# Keyboard.net
KiCad netlist of a schematic drawn in Altium Designer
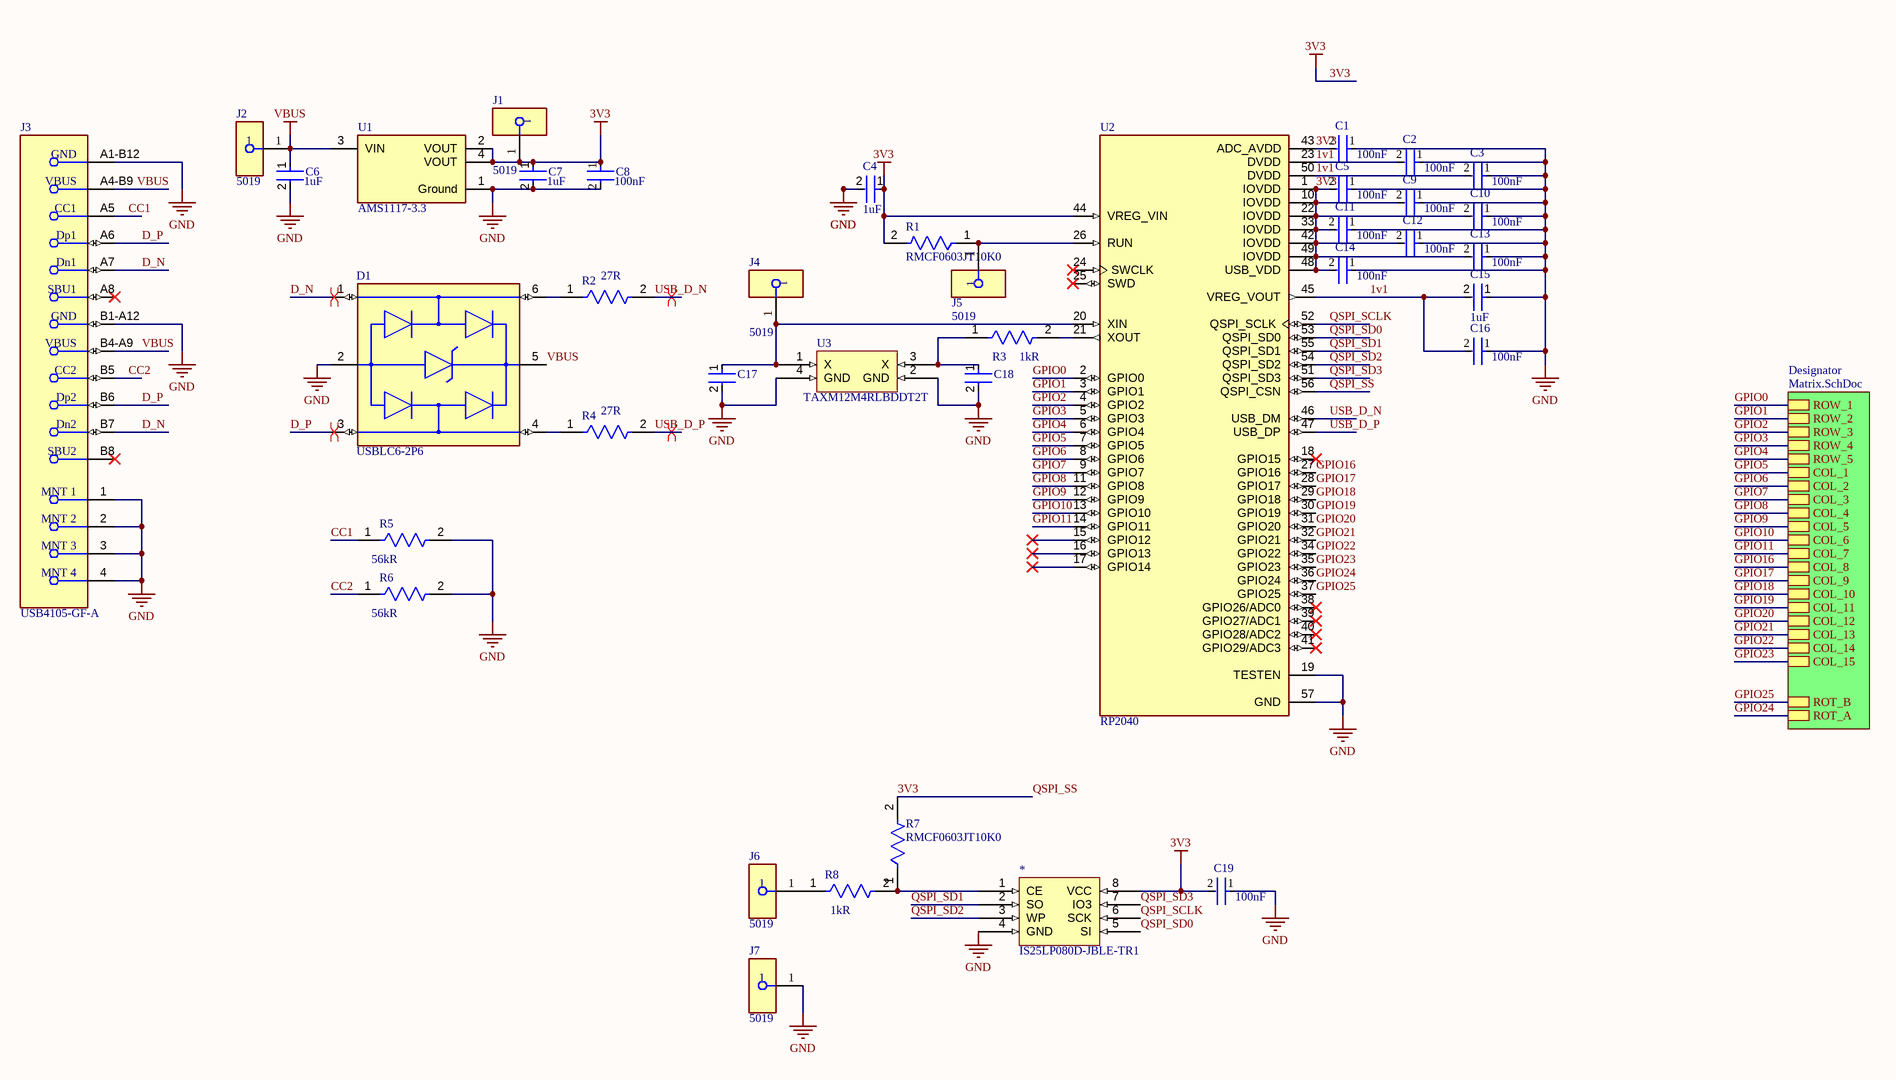
[diagram p0: Keyboard.SchDoc]

(export (version "E")
  (design (tool "Eeschema 10.0.6"))
  (components
    (comp (ref "*")
      (value "IS25LP080D-JBLE-TR1")
      (footprint "SOIC127P1030X265-8N")
      (description "Flash")
      (libsource (lib "Brian Tan") (part "New symbol 1"))
    )
    (comp (ref "C1")
      (value "GRM155R71C104KA88J")
      (footprint "FP-GRM155-0_05-MFG")
      (fields
        (field (name "VOLTAGE") "16V")
        (field (name "TOLERANCE") "10%")
        (field (name "CAPACITANCE") "100nF")
      )
      (libsource (lib "Altium Content Vault") (part "b4654b650e69147ec39a6b967a45e02"))
    )
    (comp (ref "C2")
      (value "GRM155R71C104KA88J")
      (footprint "FP-GRM155-0_05-MFG")
      (fields
        (field (name "VOLTAGE") "16V")
        (field (name "TOLERANCE") "10%")
        (field (name "CAPACITANCE") "100nF")
      )
      (libsource (lib "Altium Content Vault") (part "b4654b650e69147ec39a6b967a45e02"))
    )
    (comp (ref "C3")
      (value "GRM155R71C104KA88J")
      (footprint "FP-GRM155-0_05-MFG")
      (fields
        (field (name "VOLTAGE") "16V")
        (field (name "TOLERANCE") "10%")
        (field (name "CAPACITANCE") "100nF")
      )
      (libsource (lib "Altium Content Vault") (part "b4654b650e69147ec39a6b967a45e02"))
    )
    (comp (ref "C4")
      (value "CL10A105KO8NNNC")
      (footprint "FP-CL10-IPC_A")
      (description "Cap Ceramic 1uF 16V X5R ±10% Pad SMD 0603 +85°C T/R")
      (fields
        (field (name "CAPACITANCE") "1uF")
        (field (name "TOLERANCE") "10%")
        (field (name "VOLTAGE") "16V")
      )
      (libsource (lib "Altium Content Vault") (part "b4654b650e69147ec39a6b967a45e02"))
    )
    (comp (ref "C5")
      (value "GRM155R71C104KA88J")
      (footprint "FP-GRM155-0_05-MFG")
      (fields
        (field (name "VOLTAGE") "16V")
        (field (name "TOLERANCE") "10%")
        (field (name "CAPACITANCE") "100nF")
      )
      (libsource (lib "Altium Content Vault") (part "b4654b650e69147ec39a6b967a45e02"))
    )
    (comp (ref "C6")
      (value "CL10A105KO8NNNC")
      (footprint "FP-CL10-IPC_A")
      (description "Cap Ceramic 1uF 16V X5R ±10% Pad SMD 0603 +85°C T/R")
      (fields
        (field (name "CAPACITANCE") "1uF")
        (field (name "TOLERANCE") "10%")
        (field (name "VOLTAGE") "16V")
      )
      (libsource (lib "Altium Content Vault") (part "b4654b650e69147ec39a6b967a45e02"))
    )
    (comp (ref "C7")
      (value "CL10A105KO8NNNC")
      (footprint "FP-CL10-IPC_A")
      (description "Cap Ceramic 1uF 16V X5R ±10% Pad SMD 0603 +85°C T/R")
      (fields
        (field (name "CAPACITANCE") "1uF")
        (field (name "TOLERANCE") "10%")
        (field (name "VOLTAGE") "16V")
      )
      (libsource (lib "Altium Content Vault") (part "b4654b650e69147ec39a6b967a45e02"))
    )
    (comp (ref "C8")
      (value "GRM155R71C104KA88J")
      (footprint "FP-GRM155-0_05-MFG")
      (fields
        (field (name "VOLTAGE") "16V")
        (field (name "TOLERANCE") "10%")
        (field (name "CAPACITANCE") "100nF")
      )
      (libsource (lib "Altium Content Vault") (part "b4654b650e69147ec39a6b967a45e02"))
    )
    (comp (ref "C9")
      (value "GRM155R71C104KA88J")
      (footprint "FP-GRM155-0_05-MFG")
      (fields
        (field (name "VOLTAGE") "16V")
        (field (name "TOLERANCE") "10%")
        (field (name "CAPACITANCE") "100nF")
      )
      (libsource (lib "Altium Content Vault") (part "b4654b650e69147ec39a6b967a45e02"))
    )
    (comp (ref "C10")
      (value "GRM155R71C104KA88J")
      (footprint "FP-GRM155-0_05-MFG")
      (fields
        (field (name "VOLTAGE") "16V")
        (field (name "TOLERANCE") "10%")
        (field (name "CAPACITANCE") "100nF")
      )
      (libsource (lib "Altium Content Vault") (part "b4654b650e69147ec39a6b967a45e02"))
    )
    (comp (ref "C11")
      (value "GRM155R71C104KA88J")
      (footprint "FP-GRM155-0_05-MFG")
      (fields
        (field (name "VOLTAGE") "16V")
        (field (name "TOLERANCE") "10%")
        (field (name "CAPACITANCE") "100nF")
      )
      (libsource (lib "Altium Content Vault") (part "b4654b650e69147ec39a6b967a45e02"))
    )
    (comp (ref "C12")
      (value "GRM155R71C104KA88J")
      (footprint "FP-GRM155-0_05-MFG")
      (fields
        (field (name "VOLTAGE") "16V")
        (field (name "TOLERANCE") "10%")
        (field (name "CAPACITANCE") "100nF")
      )
      (libsource (lib "Altium Content Vault") (part "b4654b650e69147ec39a6b967a45e02"))
    )
    (comp (ref "C13")
      (value "GRM155R71C104KA88J")
      (footprint "FP-GRM155-0_05-MFG")
      (fields
        (field (name "VOLTAGE") "16V")
        (field (name "TOLERANCE") "10%")
        (field (name "CAPACITANCE") "100nF")
      )
      (libsource (lib "Altium Content Vault") (part "b4654b650e69147ec39a6b967a45e02"))
    )
    (comp (ref "C14")
      (value "GRM155R71C104KA88J")
      (footprint "FP-GRM155-0_05-MFG")
      (fields
        (field (name "VOLTAGE") "16V")
        (field (name "TOLERANCE") "10%")
        (field (name "CAPACITANCE") "100nF")
      )
      (libsource (lib "Altium Content Vault") (part "b4654b650e69147ec39a6b967a45e02"))
    )
    (comp (ref "C15")
      (value "CL10A105KO8NNNC")
      (footprint "FP-CL10-IPC_A")
      (description "Cap Ceramic 1uF 16V X5R ±10% Pad SMD 0603 +85°C T/R")
      (fields
        (field (name "CAPACITANCE") "1uF")
        (field (name "TOLERANCE") "10%")
        (field (name "VOLTAGE") "16V")
      )
      (libsource (lib "Altium Content Vault") (part "b4654b650e69147ec39a6b967a45e02"))
    )
    (comp (ref "C16")
      (value "GRM155R71C104KA88J")
      (footprint "FP-GRM155-0_05-MFG")
      (fields
        (field (name "VOLTAGE") "16V")
        (field (name "TOLERANCE") "10%")
        (field (name "CAPACITANCE") "100nF")
      )
      (libsource (lib "Altium Content Vault") (part "b4654b650e69147ec39a6b967a45e02"))
    )
    (comp (ref "C17")
      (value "GQM2195C2E320JB12D")
      (footprint "FP-GQM219-0_15-IPC_C")
      (description "Ceramic Capacitor 32pF ±5% 250VDC C0G 0805 Paper T/R")
      (libsource (lib "Altium Content Vault") (part "b4654b650e69147ec39a6b967a45e02"))
    )
    (comp (ref "C18")
      (value "GQM2195C2E320JB12D")
      (footprint "FP-GQM219-0_15-IPC_C")
      (description "Ceramic Capacitor 32pF ±5% 250VDC C0G 0805 Paper T/R")
      (libsource (lib "Altium Content Vault") (part "b4654b650e69147ec39a6b967a45e02"))
    )
    (comp (ref "C19")
      (value "GRM155R71C104KA88J")
      (footprint "FP-GRM155-0_05-MFG")
      (fields
        (field (name "VOLTAGE") "16V")
        (field (name "TOLERANCE") "10%")
        (field (name "CAPACITANCE") "100nF")
      )
      (libsource (lib "Altium Content Vault") (part "b4654b650e69147ec39a6b967a45e02"))
    )
    (comp (ref "D1")
      (value "USBLC6-2P6")
      (footprint "FP-SOT-666-MFG")
      (description "TVS DIODE 5.25V 17V SOT666")
      (libsource (lib "Altium Content Vault") (part "c871e55f7e3243d341edbd671b98d92"))
    )
    (comp (ref "J1")
      (value "5019")
      (footprint "FP-5019-MFG")
      (libsource (lib "") (part "98815daf2f2c152b0c43f5ab9800df6_2"))
    )
    (comp (ref "J2")
      (value "5019")
      (footprint "FP-5019-MFG")
      (libsource (lib "Altium Content Vault") (part "98815daf2f2c152b0c43f5ab9800df6"))
    )
    (comp (ref "J3")
      (value "USB4105-GF-A")
      (footprint "FP-USB4105-GF-A-MFG")
      (description "CONN RCPT USB2.0 TYPEC 5A")
      (fields
        (field (name "MANUFACTURER") "GCT")
        (field (name "OCTOPART") "https://octopart.com/usb4105-gf-a-gct-106627878")
      )
      (libsource (lib "Altium Content Vault") (part "e7c17a616881a82b79941196b4bec10"))
    )
    (comp (ref "J4")
      (value "5019")
      (footprint "FP-5019-MFG")
      (libsource (lib "") (part "98815daf2f2c152b0c43f5ab9800df6_2"))
    )
    (comp (ref "J5")
      (value "5019")
      (footprint "FP-5019-MFG")
      (libsource (lib "") (part "98815daf2f2c152b0c43f5ab9800df6_1"))
    )
    (comp (ref "J6")
      (value "5019")
      (footprint "FP-5019-MFG")
      (libsource (lib "Altium Content Vault") (part "98815daf2f2c152b0c43f5ab9800df6"))
    )
    (comp (ref "J7")
      (value "5019")
      (footprint "FP-5019-MFG")
      (libsource (lib "Altium Content Vault") (part "98815daf2f2c152b0c43f5ab9800df6"))
    )
    (comp (ref "R1")
      (value "RMCF0603JT10K0")
      (footprint "FP-RMCF0603-IPC_C")
      (description "10kΩ ±5% 0.1W 0603 Thick Film Chip Resistor AEC-Q200 compliant")
      (fields (field (name "TOLERANCE") "5%"))
      (libsource (lib "Altium Content Vault") (part "1029c3af85768c4190bb7ad29bc67b5"))
    )
    (comp (ref "R2")
      (value "RMCF0603FT27R0")
      (footprint "FP-RMCF0603-IPC_B")
      (description "27Ω ±1% 0.1W 0603 Thick Film Chip Resistor AEC-Q200 compliant")
      (fields (field (name "RESISTANCE") "27R") (field (name "TOLERANCE") "1%"))
      (libsource (lib "Altium Content Vault") (part "1029c3af85768c4190bb7ad29bc67b5"))
    )
    (comp (ref "R3")
      (value "RC0603FR-071KL")
      (footprint "FP-RC0603-0_55-IPC_C")
      (description "RES 1K OHM 1% 1/10W 0603")
      (fields (field (name "RESISTANCE") "1kR") (field (name "TOLERANCE") "1%"))
      (libsource (lib "Altium Content Vault") (part "1029c3af85768c4190bb7ad29bc67b5"))
    )
    (comp (ref "R4")
      (value "RMCF0603FT27R0")
      (footprint "FP-RMCF0603-IPC_B")
      (description "27Ω ±1% 0.1W 0603 Thick Film Chip Resistor AEC-Q200 compliant")
      (fields (field (name "RESISTANCE") "27R") (field (name "TOLERANCE") "1%"))
      (libsource (lib "Altium Content Vault") (part "1029c3af85768c4190bb7ad29bc67b5"))
    )
    (comp (ref "R5")
      (value "RMCF1206JT56K0")
      (footprint "FP-RMCF1206-MFG")
      (description "56kΩ ±5% 0.25W 1206 Thick Film Chip Resistor AEC-Q200 compliant")
      (fields (field (name "RESISTANCE") "56kR") (field (name "TOLERANCE") "5%"))
      (libsource (lib "Altium Content Vault") (part "1029c3af85768c4190bb7ad29bc67b5"))
    )
    (comp (ref "R6")
      (value "RMCF1206JT56K0")
      (footprint "FP-RMCF1206-MFG")
      (description "56kΩ ±5% 0.25W 1206 Thick Film Chip Resistor AEC-Q200 compliant")
      (fields (field (name "RESISTANCE") "56kR") (field (name "TOLERANCE") "5%"))
      (libsource (lib "Altium Content Vault") (part "1029c3af85768c4190bb7ad29bc67b5"))
    )
    (comp (ref "R7")
      (value "RMCF0603JT10K0")
      (footprint "FP-RMCF0603-IPC_C")
      (description "10kΩ ±5% 0.1W 0603 Thick Film Chip Resistor AEC-Q200 compliant")
      (fields (field (name "TOLERANCE") "5%"))
      (libsource (lib "Altium Content Vault") (part "1029c3af85768c4190bb7ad29bc67b5"))
    )
    (comp (ref "R8")
      (value "RC0603FR-071KL")
      (footprint "FP-RC0603-0_55-IPC_C")
      (description "RES 1K OHM 1% 1/10W 0603")
      (fields (field (name "RESISTANCE") "1kR") (field (name "TOLERANCE") "1%"))
      (libsource (lib "Altium Content Vault") (part "1029c3af85768c4190bb7ad29bc67b5"))
    )
    (comp (ref "U1")
      (value "AMS1117-3.3")
      (footprint "FP-AMS1117-IPC_C")
      (description "LDO Voltage Regulators 1A, 3.3V")
      (fields
        (field (name "OCTOPART") "https://octopart.com/ams1117-3.3-advanced+monolithic+systems-25899300")
        (field (name "MANUFACTURER") "Advanced Monolithic Systems")
      )
      (libsource (lib "Altium Content Vault") (part "8bdbb5f8e77002000e30dd2845d0354"))
    )
    (comp (ref "U2")
      (value "RP2040")
      (footprint "QFN40P700X700X90-57N")
      (description "RP2040 chip for Raspberry Pi Pico - ARM® Cortex®-M0+ MCU 32-Bit")
      (fields (field (name "MF") "Raspberry Pi"))
      (libsource (lib "Brian Tan") (part "RP2040"))
    )
    (comp (ref "U3")
      (value "TAXM12M4RLBDDT2T")
      (footprint "TAXM12M4RLBDDT2T")
      (description "Crystal 12MHz")
      (libsource (lib "Brian Tan") (part "TAXM12M4RLBDDT2T"))
    )
  )
  (nets
    (net (code "1") (name "/1v1") (class "Default")
      (node (ref "C15") (pin "2") (pinfunction "2_2") (pintype "passive"))
      (node (ref "C16") (pin "2") (pinfunction "2_2") (pintype "passive"))
      (node (ref "C2") (pin "2") (pinfunction "2_2") (pintype "passive"))
      (node (ref "C3") (pin "2") (pinfunction "2_2") (pintype "passive"))
      (node (ref "U2") (pin "23") (pinfunction "DVDD_23") (pintype "power_in"))
      (node (ref "U2") (pin "45") (pinfunction "VREG_VOUT_45") (pintype "output"))
      (node (ref "U2") (pin "50") (pinfunction "DVDD_50") (pintype "power_in"))
    )
    (net (code "2") (name "/CC1") (class "Default")
      (node (ref "J3") (pin "A5") (pinfunction "CC1_A5") (pintype "power_in"))
      (node (ref "R5") (pin "1") (pinfunction "1_1") (pintype "passive"))
    )
    (net (code "3") (name "/CC2") (class "Default")
      (node (ref "J3") (pin "B5") (pinfunction "CC2_B5") (pintype "bidirectional"))
      (node (ref "R6") (pin "1") (pinfunction "1_1") (pintype "passive"))
    )
    (net (code "4") (name "/D_N") (class "Default")
      (node (ref "D1") (pin "1") (pinfunction "I/O1_1") (pintype "bidirectional"))
      (node (ref "J3") (pin "A7") (pinfunction "Dn1_A7") (pintype "bidirectional"))
      (node (ref "J3") (pin "B7") (pinfunction "Dn2_B7") (pintype "bidirectional"))
    )
    (net (code "5") (name "/D_P") (class "Default")
      (node (ref "D1") (pin "3") (pinfunction "I/O2_3") (pintype "bidirectional"))
      (node (ref "J3") (pin "A6") (pinfunction "Dp1_A6") (pintype "bidirectional"))
      (node (ref "J3") (pin "B6") (pinfunction "Dp2_B6") (pintype "bidirectional"))
    )
    (net (code "6") (name "/GPIO0") (class "Default")
      (node (ref "U2") (pin "2") (pinfunction "GPIO0_2") (pintype "bidirectional"))
    )
    (net (code "7") (name "/GPIO1") (class "Default")
      (node (ref "U2") (pin "3") (pinfunction "GPIO1_3") (pintype "bidirectional"))
    )
    (net (code "8") (name "/GPIO2") (class "Default")
      (node (ref "U2") (pin "4") (pinfunction "GPIO2_4") (pintype "bidirectional"))
    )
    (net (code "9") (name "/GPIO3") (class "Default")
      (node (ref "U2") (pin "5") (pinfunction "GPIO3_5") (pintype "bidirectional"))
    )
    (net (code "10") (name "/GPIO4") (class "Default")
      (node (ref "U2") (pin "6") (pinfunction "GPIO4_6") (pintype "bidirectional"))
    )
    (net (code "11") (name "/GPIO5") (class "Default")
      (node (ref "U2") (pin "7") (pinfunction "GPIO5_7") (pintype "bidirectional"))
    )
    (net (code "12") (name "/GPIO6") (class "Default")
      (node (ref "U2") (pin "8") (pinfunction "GPIO6_8") (pintype "bidirectional"))
    )
    (net (code "13") (name "/GPIO7") (class "Default")
      (node (ref "U2") (pin "9") (pinfunction "GPIO7_9") (pintype "bidirectional"))
    )
    (net (code "14") (name "/GPIO8") (class "Default")
      (node (ref "U2") (pin "11") (pinfunction "GPIO8_11") (pintype "bidirectional"))
    )
    (net (code "15") (name "/GPIO9") (class "Default")
      (node (ref "U2") (pin "12") (pinfunction "GPIO9_12") (pintype "bidirectional"))
    )
    (net (code "16") (name "/GPIO10") (class "Default")
      (node (ref "U2") (pin "13") (pinfunction "GPIO10_13") (pintype "bidirectional"))
    )
    (net (code "17") (name "/GPIO11") (class "Default")
      (node (ref "U2") (pin "14") (pinfunction "GPIO11_14") (pintype "bidirectional"))
    )
    (net (code "18") (name "/GPIO16") (class "Default")
      (node (ref "U2") (pin "27") (pinfunction "GPIO16_27") (pintype "bidirectional"))
    )
    (net (code "19") (name "/GPIO17") (class "Default")
      (node (ref "U2") (pin "28") (pinfunction "GPIO17_28") (pintype "bidirectional"))
    )
    (net (code "20") (name "/GPIO18") (class "Default")
      (node (ref "U2") (pin "29") (pinfunction "GPIO18_29") (pintype "bidirectional"))
    )
    (net (code "21") (name "/GPIO19") (class "Default")
      (node (ref "U2") (pin "30") (pinfunction "GPIO19_30") (pintype "bidirectional"))
    )
    (net (code "22") (name "/GPIO20") (class "Default")
      (node (ref "U2") (pin "31") (pinfunction "GPIO20_31") (pintype "bidirectional"))
    )
    (net (code "23") (name "/GPIO21") (class "Default")
      (node (ref "U2") (pin "32") (pinfunction "GPIO21_32") (pintype "bidirectional"))
    )
    (net (code "24") (name "/GPIO22") (class "Default")
      (node (ref "U2") (pin "34") (pinfunction "GPIO22_34") (pintype "bidirectional"))
    )
    (net (code "25") (name "/GPIO23") (class "Default")
      (node (ref "U2") (pin "35") (pinfunction "GPIO23_35") (pintype "bidirectional"))
    )
    (net (code "26") (name "/GPIO24") (class "Default")
      (node (ref "U2") (pin "36") (pinfunction "GPIO24_36") (pintype "bidirectional"))
    )
    (net (code "27") (name "/GPIO25") (class "Default")
      (node (ref "U2") (pin "37") (pinfunction "GPIO25_37") (pintype "bidirectional"))
    )
    (net (code "28") (name "/QSPI_SCLK") (class "Default")
      (node (ref "*") (pin "6") (pinfunction "SCK_6") (pintype "input"))
      (node (ref "U2") (pin "52") (pinfunction "QSPI_SCLK_52") (pintype "bidirectional"))
    )
    (net (code "29") (name "/QSPI_SD0") (class "Default")
      (node (ref "*") (pin "5") (pinfunction "SI_5") (pintype "input"))
      (node (ref "U2") (pin "53") (pinfunction "QSPI_SD0_53") (pintype "bidirectional"))
    )
    (net (code "30") (name "/QSPI_SD1") (class "Default")
      (node (ref "*") (pin "2") (pinfunction "SO_2") (pintype "input"))
      (node (ref "U2") (pin "55") (pinfunction "QSPI_SD1_55") (pintype "bidirectional"))
    )
    (net (code "31") (name "/QSPI_SD2") (class "Default")
      (node (ref "*") (pin "3") (pinfunction "WP_3") (pintype "input"))
      (node (ref "U2") (pin "54") (pinfunction "QSPI_SD2_54") (pintype "bidirectional"))
    )
    (net (code "32") (name "/QSPI_SD3") (class "Default")
      (node (ref "*") (pin "7") (pinfunction "IO3_7") (pintype "input"))
      (node (ref "U2") (pin "51") (pinfunction "QSPI_SD3_51") (pintype "bidirectional"))
    )
    (net (code "33") (name "/USB_D_N") (class "Default")
      (node (ref "R2") (pin "2") (pinfunction "2_2") (pintype "passive"))
      (node (ref "U2") (pin "46") (pinfunction "USB_DM_46") (pintype "bidirectional"))
    )
    (net (code "34") (name "/USB_D_P") (class "Default")
      (node (ref "R4") (pin "2") (pinfunction "2_2") (pintype "passive"))
      (node (ref "U2") (pin "47") (pinfunction "USB_DP_47") (pintype "bidirectional"))
    )
    (net (code "35") (name "3V3") (class "Default")
      (node (ref "*") (pin "8") (pinfunction "VCC_8") (pintype "input"))
      (node (ref "C1") (pin "2") (pinfunction "2_2") (pintype "passive"))
      (node (ref "C10") (pin "2") (pinfunction "2_2") (pintype "passive"))
      (node (ref "C11") (pin "2") (pinfunction "2_2") (pintype "passive"))
      (node (ref "C12") (pin "2") (pinfunction "2_2") (pintype "passive"))
      (node (ref "C13") (pin "2") (pinfunction "2_2") (pintype "passive"))
      (node (ref "C14") (pin "2") (pinfunction "2_2") (pintype "passive"))
      (node (ref "C19") (pin "2") (pinfunction "2_2") (pintype "passive"))
      (node (ref "C4") (pin "1") (pinfunction "1_1") (pintype "passive"))
      (node (ref "C5") (pin "2") (pinfunction "2_2") (pintype "passive"))
      (node (ref "C7") (pin "1") (pinfunction "1_1") (pintype "passive"))
      (node (ref "C8") (pin "1") (pinfunction "1_1") (pintype "passive"))
      (node (ref "C9") (pin "2") (pinfunction "2_2") (pintype "passive"))
      (node (ref "J1") (pin "1") (pinfunction "1_1") (pintype "passive"))
      (node (ref "R1") (pin "2") (pinfunction "2_2") (pintype "passive"))
      (node (ref "R7") (pin "2") (pinfunction "2_2") (pintype "passive"))
      (node (ref "U1") (pin "2") (pinfunction "VOUT_2") (pintype "passive"))
      (node (ref "U1") (pin "4") (pinfunction "VOUT_4") (pintype "passive"))
      (node (ref "U2") (pin "1") (pinfunction "IOVDD_1") (pintype "power_in"))
      (node (ref "U2") (pin "10") (pinfunction "IOVDD_10") (pintype "power_in"))
      (node (ref "U2") (pin "22") (pinfunction "IOVDD_22") (pintype "power_in"))
      (node (ref "U2") (pin "33") (pinfunction "IOVDD_33") (pintype "power_in"))
      (node (ref "U2") (pin "42") (pinfunction "IOVDD_42") (pintype "power_in"))
      (node (ref "U2") (pin "43") (pinfunction "ADC_AVDD_43") (pintype "power_in"))
      (node (ref "U2") (pin "44") (pinfunction "VREG_VIN_44") (pintype "input"))
      (node (ref "U2") (pin "48") (pinfunction "USB_VDD_48") (pintype "power_in"))
      (node (ref "U2") (pin "49") (pinfunction "IOVDD_49") (pintype "power_in"))
      (node (ref "U2") (pin "56") (pinfunction "QSPI_CSN_56") (pintype "bidirectional"))
    )
    (net (code "36") (name "GND") (class "Default")
      (node (ref "*") (pin "4") (pinfunction "GND_4") (pintype "input"))
      (node (ref "C1") (pin "1") (pinfunction "1_1") (pintype "passive"))
      (node (ref "C10") (pin "1") (pinfunction "1_1") (pintype "passive"))
      (node (ref "C11") (pin "1") (pinfunction "1_1") (pintype "passive"))
      (node (ref "C12") (pin "1") (pinfunction "1_1") (pintype "passive"))
      (node (ref "C13") (pin "1") (pinfunction "1_1") (pintype "passive"))
      (node (ref "C14") (pin "1") (pinfunction "1_1") (pintype "passive"))
      (node (ref "C15") (pin "1") (pinfunction "1_1") (pintype "passive"))
      (node (ref "C16") (pin "1") (pinfunction "1_1") (pintype "passive"))
      (node (ref "C17") (pin "2") (pinfunction "2_2") (pintype "passive"))
      (node (ref "C18") (pin "2") (pinfunction "2_2") (pintype "passive"))
      (node (ref "C19") (pin "1") (pinfunction "1_1") (pintype "passive"))
      (node (ref "C2") (pin "1") (pinfunction "1_1") (pintype "passive"))
      (node (ref "C3") (pin "1") (pinfunction "1_1") (pintype "passive"))
      (node (ref "C4") (pin "2") (pinfunction "2_2") (pintype "passive"))
      (node (ref "C5") (pin "1") (pinfunction "1_1") (pintype "passive"))
      (node (ref "C6") (pin "2") (pinfunction "2_2") (pintype "passive"))
      (node (ref "C7") (pin "2") (pinfunction "2_2") (pintype "passive"))
      (node (ref "C8") (pin "2") (pinfunction "2_2") (pintype "passive"))
      (node (ref "C9") (pin "1") (pinfunction "1_1") (pintype "passive"))
      (node (ref "D1") (pin "2") (pinfunction "GND_2") (pintype "power_in"))
      (node (ref "J3") (pin "1") (pinfunction "MNT_1_1") (pintype "power_in"))
      (node (ref "J3") (pin "2") (pinfunction "MNT_2_2") (pintype "power_in"))
      (node (ref "J3") (pin "3") (pinfunction "MNT_3_3") (pintype "power_in"))
      (node (ref "J3") (pin "4") (pinfunction "MNT_4_4") (pintype "power_in"))
      (node (ref "J3") (pin "A1-B12") (pinfunction "GND_A1-B12") (pintype "power_in"))
      (node (ref "J3") (pin "B1-A12") (pinfunction "GND_B1-A12") (pintype "bidirectional"))
      (node (ref "J7") (pin "1") (pinfunction "1_1") (pintype "passive"))
      (node (ref "R5") (pin "2") (pinfunction "2_2") (pintype "passive"))
      (node (ref "R6") (pin "2") (pinfunction "2_2") (pintype "passive"))
      (node (ref "U1") (pin "1") (pinfunction "Ground_1") (pintype "power_in"))
      (node (ref "U2") (pin "19") (pinfunction "TESTEN_19") (pintype "passive"))
      (node (ref "U2") (pin "57") (pinfunction "GND_57") (pintype "power_in"))
      (node (ref "U3") (pin "2") (pinfunction "GND_2") (pintype "input"))
      (node (ref "U3") (pin "4") (pinfunction "GND_4") (pintype "input"))
    )
    (net (code "37") (name "Net-(*-CE)") (class "Default")
      (node (ref "*") (pin "1") (pinfunction "CE_1") (pintype "input"))
      (node (ref "R7") (pin "1") (pinfunction "1_1") (pintype "passive"))
      (node (ref "R8") (pin "2") (pinfunction "2_2") (pintype "passive"))
    )
    (net (code "38") (name "Net-(C18-Pad1)") (class "Default")
      (node (ref "C18") (pin "1") (pinfunction "1_1") (pintype "passive"))
      (node (ref "R3") (pin "1") (pinfunction "1_1") (pintype "passive"))
      (node (ref "U3") (pin "3") (pinfunction "X_3") (pintype "input"))
    )
    (net (code "39") (name "Net-(D1-I{slash}O1-Pad6)") (class "Default")
      (node (ref "D1") (pin "6") (pinfunction "I/O1_6") (pintype "bidirectional"))
      (node (ref "R2") (pin "1") (pinfunction "1_1") (pintype "passive"))
    )
    (net (code "40") (name "Net-(D1-I{slash}O2-Pad4)") (class "Default")
      (node (ref "D1") (pin "4") (pinfunction "I/O2_4") (pintype "bidirectional"))
      (node (ref "R4") (pin "1") (pinfunction "1_1") (pintype "passive"))
    )
    (net (code "41") (name "Net-(J6-Pad1)") (class "Default")
      (node (ref "J6") (pin "1") (pinfunction "1_1") (pintype "passive"))
      (node (ref "R8") (pin "1") (pinfunction "1_1") (pintype "passive"))
    )
    (net (code "42") (name "Net-(U2-RUN)") (class "Default")
      (node (ref "J5") (pin "1") (pinfunction "1_1") (pintype "passive"))
      (node (ref "R1") (pin "1") (pinfunction "1_1") (pintype "passive"))
      (node (ref "U2") (pin "26") (pinfunction "RUN_26") (pintype "input"))
    )
    (net (code "43") (name "Net-(U2-XIN)") (class "Default")
      (node (ref "C17") (pin "1") (pinfunction "1_1") (pintype "passive"))
      (node (ref "J4") (pin "1") (pinfunction "1_1") (pintype "passive"))
      (node (ref "U2") (pin "20") (pinfunction "XIN_20") (pintype "input"))
      (node (ref "U3") (pin "1") (pinfunction "X_1") (pintype "input"))
    )
    (net (code "44") (name "Net-(U2-XOUT)") (class "Default")
      (node (ref "R3") (pin "2") (pinfunction "2_2") (pintype "passive"))
      (node (ref "U2") (pin "21") (pinfunction "XOUT_21") (pintype "output"))
    )
    (net (code "45") (name "VBUS") (class "Default")
      (node (ref "C6") (pin "1") (pinfunction "1_1") (pintype "passive"))
      (node (ref "D1") (pin "5") (pinfunction "VBUS_5") (pintype "power_in"))
      (node (ref "J2") (pin "1") (pinfunction "1_1") (pintype "passive"))
      (node (ref "J3") (pin "A4-B9") (pinfunction "VBUS_A4-B9") (pintype "power_in"))
      (node (ref "J3") (pin "B4-A9") (pinfunction "VBUS_B4-A9") (pintype "bidirectional"))
      (node (ref "U1") (pin "3") (pinfunction "VIN_3") (pintype "power_in"))
    )
    (net (code "46") (name "unconnected-(J3-SBU1-PadA8)") (class "Default")
      (node (ref "J3") (pin "A8") (pinfunction "SBU1_A8") (pintype "bidirectional+no_connect"))
    )
    (net (code "47") (name "unconnected-(J3-SBU2-PadB8)") (class "Default")
      (node (ref "J3") (pin "B8") (pinfunction "SBU2_B8") (pintype "power_in+no_connect"))
    )
    (net (code "48") (name "unconnected-(U2-GPIO12-Pad15)") (class "Default")
      (node (ref "U2") (pin "15") (pinfunction "GPIO12_15") (pintype "bidirectional+no_connect"))
    )
    (net (code "49") (name "unconnected-(U2-GPIO13-Pad16)") (class "Default")
      (node (ref "U2") (pin "16") (pinfunction "GPIO13_16") (pintype "bidirectional+no_connect"))
    )
    (net (code "50") (name "unconnected-(U2-GPIO14-Pad17)") (class "Default")
      (node (ref "U2") (pin "17") (pinfunction "GPIO14_17") (pintype "bidirectional+no_connect"))
    )
    (net (code "51") (name "unconnected-(U2-GPIO15-Pad18)") (class "Default")
      (node (ref "U2") (pin "18") (pinfunction "GPIO15_18") (pintype "bidirectional+no_connect"))
    )
    (net (code "52") (name "unconnected-(U2-GPIO26{slash}ADC0-Pad38)") (class "Default")
      (node (ref "U2") (pin "38") (pinfunction "GPIO26/ADC0_38") (pintype "bidirectional+no_connect"))
    )
    (net (code "53") (name "unconnected-(U2-GPIO27{slash}ADC1-Pad39)") (class "Default")
      (node (ref "U2") (pin "39") (pinfunction "GPIO27/ADC1_39") (pintype "bidirectional+no_connect"))
    )
    (net (code "54") (name "unconnected-(U2-GPIO28{slash}ADC2-Pad40)") (class "Default")
      (node (ref "U2") (pin "40") (pinfunction "GPIO28/ADC2_40") (pintype "bidirectional+no_connect"))
    )
    (net (code "55") (name "unconnected-(U2-GPIO29{slash}ADC3-Pad41)") (class "Default")
      (node (ref "U2") (pin "41") (pinfunction "GPIO29/ADC3_41") (pintype "bidirectional+no_connect"))
    )
    (net (code "56") (name "unconnected-(U2-SWCLK-Pad24)") (class "Default")
      (node (ref "U2") (pin "24") (pinfunction "SWCLK_24") (pintype "input+no_connect"))
    )
    (net (code "57") (name "unconnected-(U2-SWD-Pad25)") (class "Default")
      (node (ref "U2") (pin "25") (pinfunction "SWD_25") (pintype "bidirectional+no_connect"))
    )
  )
)
